# Eth_Switch_RJ45.net
KiCad netlist of a schematic drawn in Altium Designer
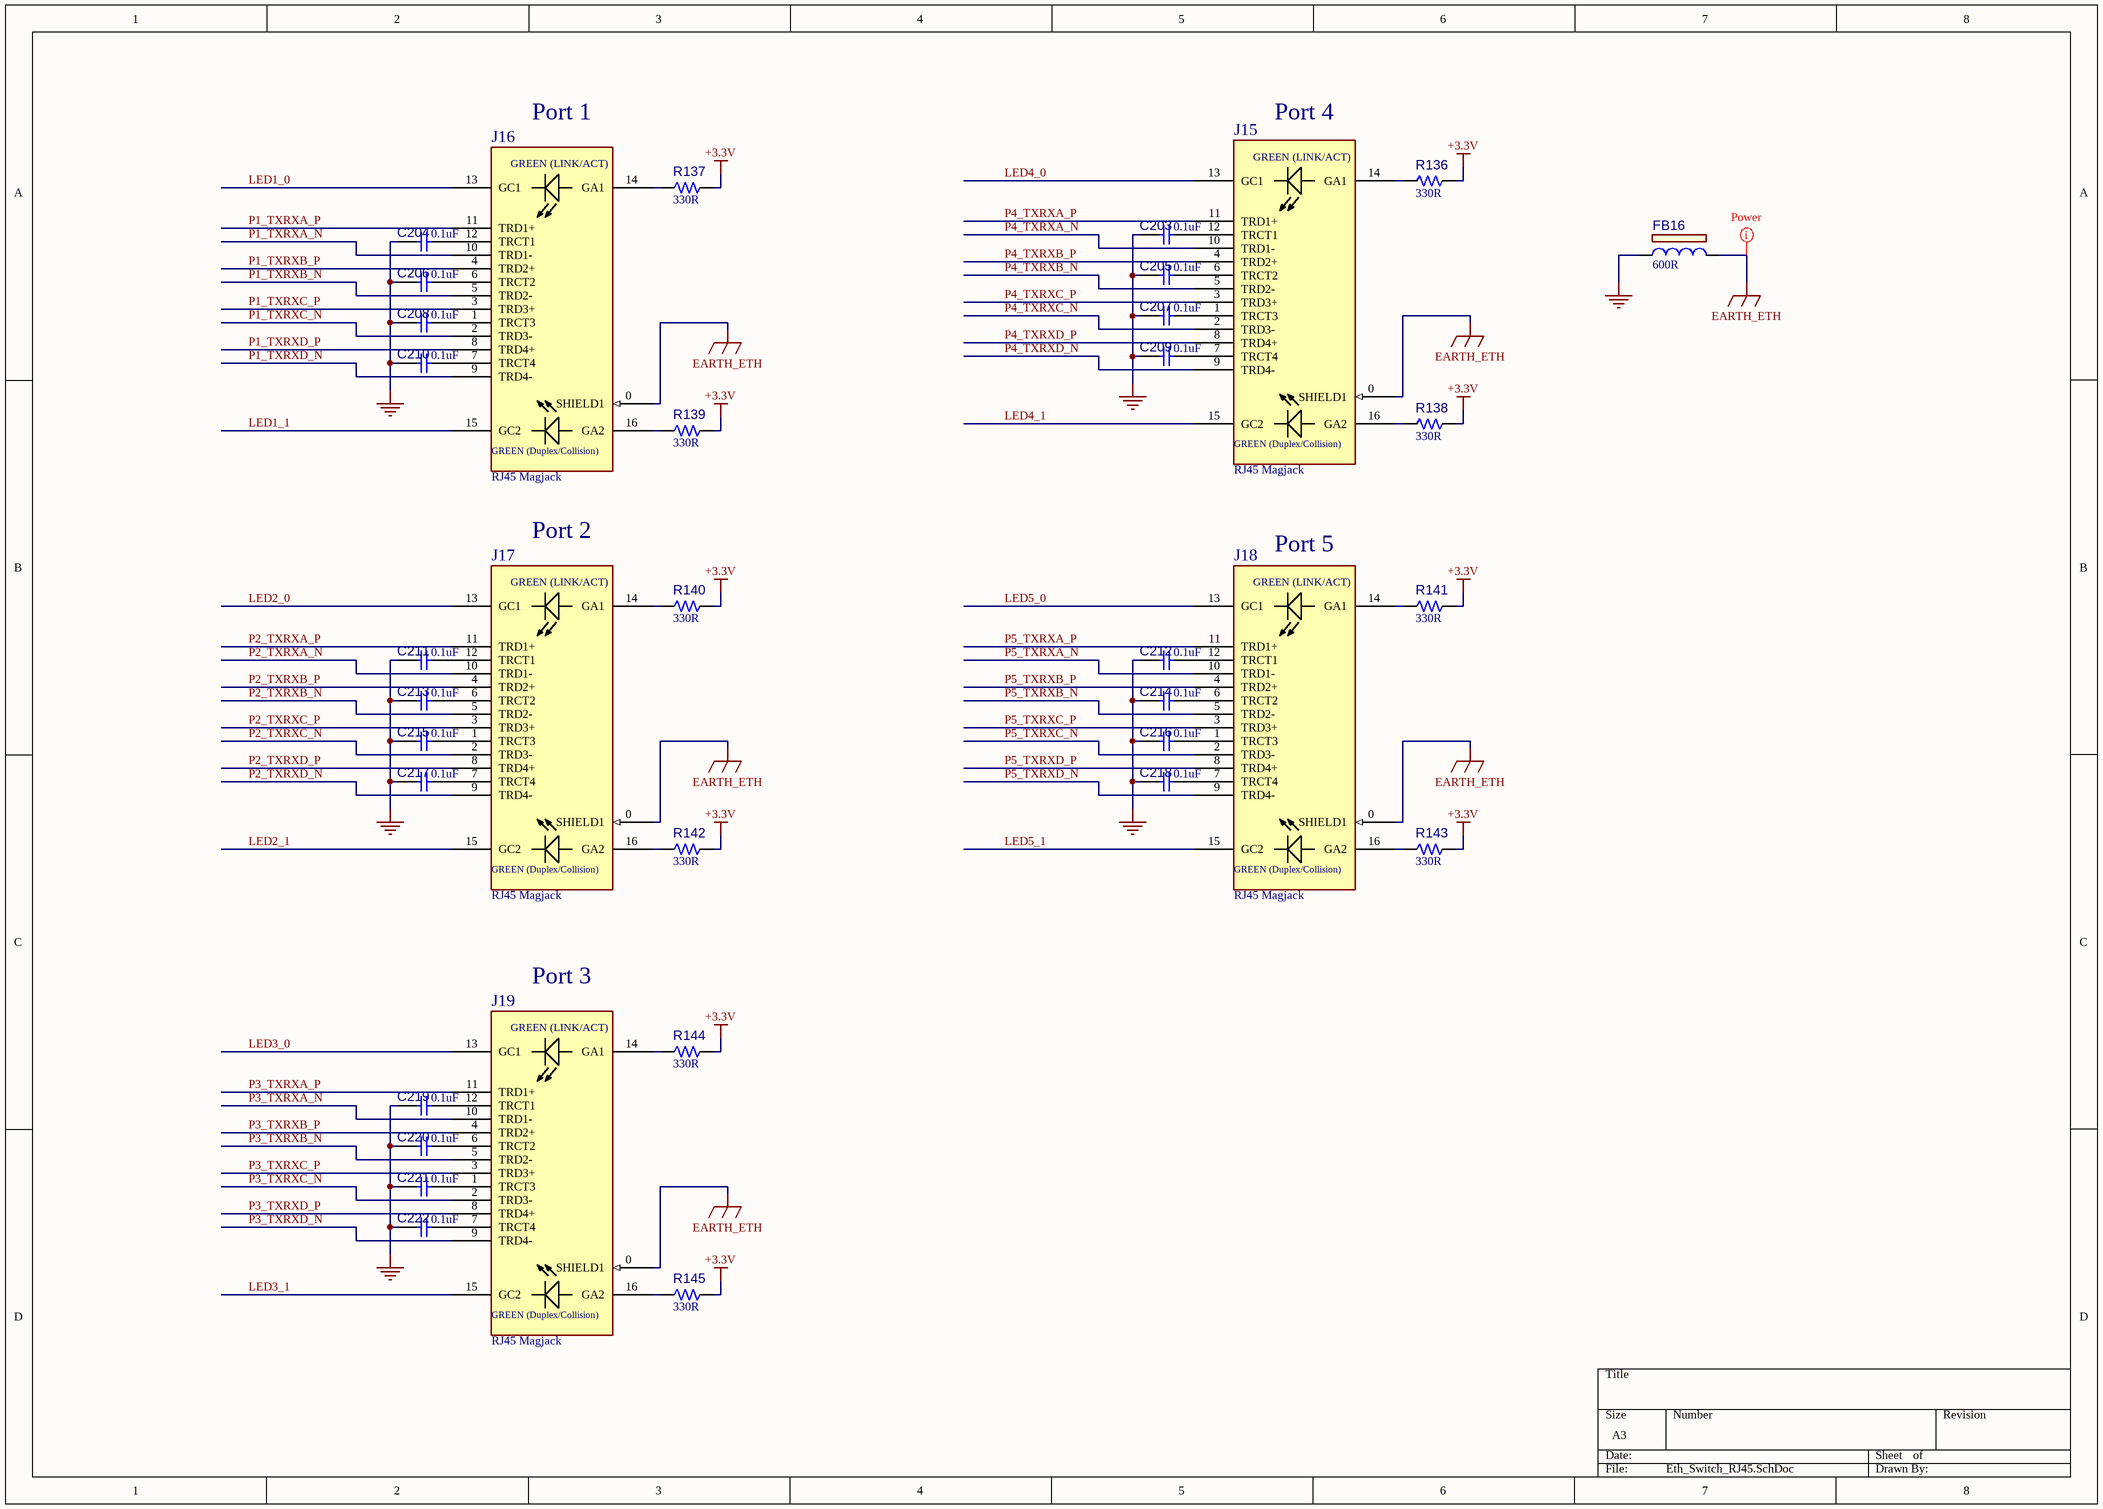
[diagram p0: Eth_Switch_RJ45.SchDoc]

(export (version "E")
  (design (tool "Eeschema 10.0.6"))
  (components
    (comp (ref "C203")
      (value "0.1uF")
      (footprint "Ultrascale_PcbLib:CAP_C_0402")
      (description "Capacitor")
      (fields
        (field (name "VOLTAGE") "50V")
        (field (name "TOLERANCE") "10%")
        (field (name "OWNER") "Jamus Griego")
      )
      (libsource (lib "Ultrascale_SchLib") (part "Capacitor NP"))
    )
    (comp (ref "C204")
      (value "0.1uF")
      (footprint "Ultrascale_PcbLib:CAP_C_0402")
      (description "Capacitor")
      (fields
        (field (name "VOLTAGE") "50V")
        (field (name "TOLERANCE") "10%")
        (field (name "OWNER") "Jamus Griego")
      )
      (libsource (lib "Ultrascale_SchLib") (part "Capacitor NP"))
    )
    (comp (ref "C205")
      (value "0.1uF")
      (footprint "Ultrascale_PcbLib:CAP_C_0402")
      (description "Capacitor")
      (fields
        (field (name "VOLTAGE") "50V")
        (field (name "TOLERANCE") "10%")
        (field (name "OWNER") "Jamus Griego")
      )
      (libsource (lib "Ultrascale_SchLib") (part "Capacitor NP"))
    )
    (comp (ref "C206")
      (value "0.1uF")
      (footprint "Ultrascale_PcbLib:CAP_C_0402")
      (description "Capacitor")
      (fields
        (field (name "VOLTAGE") "50V")
        (field (name "TOLERANCE") "10%")
        (field (name "OWNER") "Jamus Griego")
      )
      (libsource (lib "Ultrascale_SchLib") (part "Capacitor NP"))
    )
    (comp (ref "C207")
      (value "0.1uF")
      (footprint "Ultrascale_PcbLib:CAP_C_0402")
      (description "Capacitor")
      (fields
        (field (name "VOLTAGE") "50V")
        (field (name "TOLERANCE") "10%")
        (field (name "OWNER") "Jamus Griego")
      )
      (libsource (lib "Ultrascale_SchLib") (part "Capacitor NP"))
    )
    (comp (ref "C208")
      (value "0.1uF")
      (footprint "Ultrascale_PcbLib:CAP_C_0402")
      (description "Capacitor")
      (fields
        (field (name "VOLTAGE") "50V")
        (field (name "TOLERANCE") "10%")
        (field (name "OWNER") "Jamus Griego")
      )
      (libsource (lib "Ultrascale_SchLib") (part "Capacitor NP"))
    )
    (comp (ref "C209")
      (value "0.1uF")
      (footprint "Ultrascale_PcbLib:CAP_C_0402")
      (description "Capacitor")
      (fields
        (field (name "VOLTAGE") "50V")
        (field (name "TOLERANCE") "10%")
        (field (name "OWNER") "Jamus Griego")
      )
      (libsource (lib "Ultrascale_SchLib") (part "Capacitor NP"))
    )
    (comp (ref "C210")
      (value "0.1uF")
      (footprint "Ultrascale_PcbLib:CAP_C_0402")
      (description "Capacitor")
      (fields
        (field (name "VOLTAGE") "50V")
        (field (name "TOLERANCE") "10%")
        (field (name "OWNER") "Jamus Griego")
      )
      (libsource (lib "Ultrascale_SchLib") (part "Capacitor NP"))
    )
    (comp (ref "C211")
      (value "0.1uF")
      (footprint "Ultrascale_PcbLib:CAP_C_0402")
      (description "Capacitor")
      (fields
        (field (name "VOLTAGE") "50V")
        (field (name "TOLERANCE") "10%")
        (field (name "OWNER") "Jamus Griego")
      )
      (libsource (lib "Ultrascale_SchLib") (part "Capacitor NP"))
    )
    (comp (ref "C212")
      (value "0.1uF")
      (footprint "Ultrascale_PcbLib:CAP_C_0402")
      (description "Capacitor")
      (fields
        (field (name "VOLTAGE") "50V")
        (field (name "TOLERANCE") "10%")
        (field (name "OWNER") "Jamus Griego")
      )
      (libsource (lib "Ultrascale_SchLib") (part "Capacitor NP"))
    )
    (comp (ref "C213")
      (value "0.1uF")
      (footprint "Ultrascale_PcbLib:CAP_C_0402")
      (description "Capacitor")
      (fields
        (field (name "VOLTAGE") "50V")
        (field (name "TOLERANCE") "10%")
        (field (name "OWNER") "Jamus Griego")
      )
      (libsource (lib "Ultrascale_SchLib") (part "Capacitor NP"))
    )
    (comp (ref "C214")
      (value "0.1uF")
      (footprint "Ultrascale_PcbLib:CAP_C_0402")
      (description "Capacitor")
      (fields
        (field (name "VOLTAGE") "50V")
        (field (name "TOLERANCE") "10%")
        (field (name "OWNER") "Jamus Griego")
      )
      (libsource (lib "Ultrascale_SchLib") (part "Capacitor NP"))
    )
    (comp (ref "C215")
      (value "0.1uF")
      (footprint "Ultrascale_PcbLib:CAP_C_0402")
      (description "Capacitor")
      (fields
        (field (name "VOLTAGE") "50V")
        (field (name "TOLERANCE") "10%")
        (field (name "OWNER") "Jamus Griego")
      )
      (libsource (lib "Ultrascale_SchLib") (part "Capacitor NP"))
    )
    (comp (ref "C216")
      (value "0.1uF")
      (footprint "Ultrascale_PcbLib:CAP_C_0402")
      (description "Capacitor")
      (fields
        (field (name "VOLTAGE") "50V")
        (field (name "TOLERANCE") "10%")
        (field (name "OWNER") "Jamus Griego")
      )
      (libsource (lib "Ultrascale_SchLib") (part "Capacitor NP"))
    )
    (comp (ref "C217")
      (value "0.1uF")
      (footprint "Ultrascale_PcbLib:CAP_C_0402")
      (description "Capacitor")
      (fields
        (field (name "VOLTAGE") "50V")
        (field (name "TOLERANCE") "10%")
        (field (name "OWNER") "Jamus Griego")
      )
      (libsource (lib "Ultrascale_SchLib") (part "Capacitor NP"))
    )
    (comp (ref "C218")
      (value "0.1uF")
      (footprint "Ultrascale_PcbLib:CAP_C_0402")
      (description "Capacitor")
      (fields
        (field (name "VOLTAGE") "50V")
        (field (name "TOLERANCE") "10%")
        (field (name "OWNER") "Jamus Griego")
      )
      (libsource (lib "Ultrascale_SchLib") (part "Capacitor NP"))
    )
    (comp (ref "C219")
      (value "0.1uF")
      (footprint "Ultrascale_PcbLib:CAP_C_0402")
      (description "Capacitor")
      (fields
        (field (name "VOLTAGE") "50V")
        (field (name "TOLERANCE") "10%")
        (field (name "OWNER") "Jamus Griego")
      )
      (libsource (lib "Ultrascale_SchLib") (part "Capacitor NP"))
    )
    (comp (ref "C220")
      (value "0.1uF")
      (footprint "Ultrascale_PcbLib:CAP_C_0402")
      (description "Capacitor")
      (fields
        (field (name "VOLTAGE") "50V")
        (field (name "TOLERANCE") "10%")
        (field (name "OWNER") "Jamus Griego")
      )
      (libsource (lib "Ultrascale_SchLib") (part "Capacitor NP"))
    )
    (comp (ref "C221")
      (value "0.1uF")
      (footprint "Ultrascale_PcbLib:CAP_C_0402")
      (description "Capacitor")
      (fields
        (field (name "VOLTAGE") "50V")
        (field (name "TOLERANCE") "10%")
        (field (name "OWNER") "Jamus Griego")
      )
      (libsource (lib "Ultrascale_SchLib") (part "Capacitor NP"))
    )
    (comp (ref "C222")
      (value "0.1uF")
      (footprint "Ultrascale_PcbLib:CAP_C_0402")
      (description "Capacitor")
      (fields
        (field (name "VOLTAGE") "50V")
        (field (name "TOLERANCE") "10%")
        (field (name "OWNER") "Jamus Griego")
      )
      (libsource (lib "Ultrascale_SchLib") (part "Capacitor NP"))
    )
    (comp (ref "FB16")
      (value "600R")
      (footprint "Ultrascale_PcbLib:IND_C_0805")
      (fields (field (name "Comment") "Ferrite Bead") (field (name "OWNER") "Randolph Sobrepena"))
      (libsource (lib "Ultrascale_SchLib") (part "Ferrite Bead"))
    )
    (comp (ref "J15")
      (value "RJ45 Magjack")
      (footprint "Ultrascale_PcbLib:CON_MODULAR_RJ45_TH_RA_RJMG2012211A0FR")
      (description "CON RJ-45 RJMG2012211A0FR")
      (libsource (lib "Ultrascale_SchLib") (part "CON RJ-45 RJMG2012211A0FR"))
    )
    (comp (ref "J16")
      (value "RJ45 Magjack")
      (footprint "Ultrascale_PcbLib:CON_MODULAR_RJ45_TH_RA_RJMG2012211A0FR")
      (description "CON RJ-45 RJMG2012211A0FR")
      (libsource (lib "Ultrascale_SchLib") (part "CON RJ-45 RJMG2012211A0FR"))
    )
    (comp (ref "J17")
      (value "RJ45 Magjack")
      (footprint "Ultrascale_PcbLib:CON_MODULAR_RJ45_TH_RA_RJMG2012211A0FR")
      (description "CON RJ-45 RJMG2012211A0FR")
      (libsource (lib "Ultrascale_SchLib") (part "CON RJ-45 RJMG2012211A0FR"))
    )
    (comp (ref "J18")
      (value "RJ45 Magjack")
      (footprint "Ultrascale_PcbLib:CON_MODULAR_RJ45_TH_RA_RJMG2012211A0FR")
      (description "CON RJ-45 RJMG2012211A0FR")
      (libsource (lib "Ultrascale_SchLib") (part "CON RJ-45 RJMG2012211A0FR"))
    )
    (comp (ref "J19")
      (value "RJ45 Magjack")
      (footprint "Ultrascale_PcbLib:CON_MODULAR_RJ45_TH_RA_RJMG2012211A0FR")
      (description "CON RJ-45 RJMG2012211A0FR")
      (libsource (lib "Ultrascale_SchLib") (part "CON RJ-45 RJMG2012211A0FR"))
    )
    (comp (ref "R136")
      (value "330R")
      (footprint "Ultrascale_PcbLib:RES_C_0603")
      (description "Resistor")
      (fields (field (name "TOLERANCE") "5%") (field (name "VOLTAGE") "75V"))
      (libsource (lib "Ultrascale_SchLib") (part "Resistor"))
    )
    (comp (ref "R137")
      (value "330R")
      (footprint "Ultrascale_PcbLib:RES_C_0603")
      (description "Resistor")
      (fields (field (name "TOLERANCE") "5%") (field (name "VOLTAGE") "75V"))
      (libsource (lib "Ultrascale_SchLib") (part "Resistor"))
    )
    (comp (ref "R138")
      (value "330R")
      (footprint "Ultrascale_PcbLib:RES_C_0603")
      (description "Resistor")
      (fields (field (name "TOLERANCE") "5%") (field (name "VOLTAGE") "75V"))
      (libsource (lib "Ultrascale_SchLib") (part "Resistor"))
    )
    (comp (ref "R139")
      (value "330R")
      (footprint "Ultrascale_PcbLib:RES_C_0603")
      (description "Resistor")
      (fields (field (name "TOLERANCE") "5%") (field (name "VOLTAGE") "75V"))
      (libsource (lib "Ultrascale_SchLib") (part "Resistor"))
    )
    (comp (ref "R140")
      (value "330R")
      (footprint "Ultrascale_PcbLib:RES_C_0603")
      (description "Resistor")
      (fields (field (name "TOLERANCE") "5%") (field (name "VOLTAGE") "75V"))
      (libsource (lib "Ultrascale_SchLib") (part "Resistor"))
    )
    (comp (ref "R141")
      (value "330R")
      (footprint "Ultrascale_PcbLib:RES_C_0603")
      (description "Resistor")
      (fields (field (name "TOLERANCE") "5%") (field (name "VOLTAGE") "75V"))
      (libsource (lib "Ultrascale_SchLib") (part "Resistor"))
    )
    (comp (ref "R142")
      (value "330R")
      (footprint "Ultrascale_PcbLib:RES_C_0603")
      (description "Resistor")
      (fields (field (name "TOLERANCE") "5%") (field (name "VOLTAGE") "75V"))
      (libsource (lib "Ultrascale_SchLib") (part "Resistor"))
    )
    (comp (ref "R143")
      (value "330R")
      (footprint "Ultrascale_PcbLib:RES_C_0603")
      (description "Resistor")
      (fields (field (name "TOLERANCE") "5%") (field (name "VOLTAGE") "75V"))
      (libsource (lib "Ultrascale_SchLib") (part "Resistor"))
    )
    (comp (ref "R144")
      (value "330R")
      (footprint "Ultrascale_PcbLib:RES_C_0603")
      (description "Resistor")
      (fields (field (name "TOLERANCE") "5%") (field (name "VOLTAGE") "75V"))
      (libsource (lib "Ultrascale_SchLib") (part "Resistor"))
    )
    (comp (ref "R145")
      (value "330R")
      (footprint "Ultrascale_PcbLib:RES_C_0603")
      (description "Resistor")
      (fields (field (name "TOLERANCE") "5%") (field (name "VOLTAGE") "75V"))
      (libsource (lib "Ultrascale_SchLib") (part "Resistor"))
    )
  )
  (nets
    (net (code "1") (name "+3.3V") (class "Default")
      (node (ref "R136") (pin "2") (pinfunction "2_2") (pintype "passive"))
      (node (ref "R137") (pin "2") (pinfunction "2_2") (pintype "passive"))
      (node (ref "R138") (pin "2") (pinfunction "2_2") (pintype "passive"))
      (node (ref "R139") (pin "2") (pinfunction "2_2") (pintype "passive"))
      (node (ref "R140") (pin "2") (pinfunction "2_2") (pintype "passive"))
      (node (ref "R141") (pin "2") (pinfunction "2_2") (pintype "passive"))
      (node (ref "R142") (pin "2") (pinfunction "2_2") (pintype "passive"))
      (node (ref "R143") (pin "2") (pinfunction "2_2") (pintype "passive"))
      (node (ref "R144") (pin "2") (pinfunction "2_2") (pintype "passive"))
      (node (ref "R145") (pin "2") (pinfunction "2_2") (pintype "passive"))
    )
    (net (code "2") (name "/LED1_0") (class "Default")
      (node (ref "J16") (pin "13") (pinfunction "GC1_13") (pintype "passive"))
    )
    (net (code "3") (name "/LED1_1") (class "Default")
      (node (ref "J16") (pin "15") (pinfunction "GC2_15") (pintype "passive"))
    )
    (net (code "4") (name "/LED2_0") (class "Default")
      (node (ref "J17") (pin "13") (pinfunction "GC1_13") (pintype "passive"))
    )
    (net (code "5") (name "/LED2_1") (class "Default")
      (node (ref "J17") (pin "15") (pinfunction "GC2_15") (pintype "passive"))
    )
    (net (code "6") (name "/LED3_0") (class "Default")
      (node (ref "J19") (pin "13") (pinfunction "GC1_13") (pintype "passive"))
    )
    (net (code "7") (name "/LED3_1") (class "Default")
      (node (ref "J19") (pin "15") (pinfunction "GC2_15") (pintype "passive"))
    )
    (net (code "8") (name "/LED4_0") (class "Default")
      (node (ref "J15") (pin "13") (pinfunction "GC1_13") (pintype "passive"))
    )
    (net (code "9") (name "/LED4_1") (class "Default")
      (node (ref "J15") (pin "15") (pinfunction "GC2_15") (pintype "passive"))
    )
    (net (code "10") (name "/LED5_0") (class "Default")
      (node (ref "J18") (pin "13") (pinfunction "GC1_13") (pintype "passive"))
    )
    (net (code "11") (name "/LED5_1") (class "Default")
      (node (ref "J18") (pin "15") (pinfunction "GC2_15") (pintype "passive"))
    )
    (net (code "12") (name "/P1_TXRXA_N") (class "Default")
      (node (ref "J16") (pin "10") (pinfunction "TRD1-_10") (pintype "passive"))
    )
    (net (code "13") (name "/P1_TXRXA_P") (class "Default")
      (node (ref "J16") (pin "11") (pinfunction "TRD1+_11") (pintype "passive"))
    )
    (net (code "14") (name "/P1_TXRXB_N") (class "Default")
      (node (ref "J16") (pin "5") (pinfunction "TRD2-_5") (pintype "passive"))
    )
    (net (code "15") (name "/P1_TXRXB_P") (class "Default")
      (node (ref "J16") (pin "4") (pinfunction "TRD2+_4") (pintype "passive"))
    )
    (net (code "16") (name "/P1_TXRXC_N") (class "Default")
      (node (ref "J16") (pin "2") (pinfunction "TRD3-_2") (pintype "passive"))
    )
    (net (code "17") (name "/P1_TXRXC_P") (class "Default")
      (node (ref "J16") (pin "3") (pinfunction "TRD3+_3") (pintype "passive"))
    )
    (net (code "18") (name "/P1_TXRXD_N") (class "Default")
      (node (ref "J16") (pin "9") (pinfunction "TRD4-_9") (pintype "passive"))
    )
    (net (code "19") (name "/P1_TXRXD_P") (class "Default")
      (node (ref "J16") (pin "8") (pinfunction "TRD4+_8") (pintype "passive"))
    )
    (net (code "20") (name "/P2_TXRXA_N") (class "Default")
      (node (ref "J17") (pin "10") (pinfunction "TRD1-_10") (pintype "passive"))
    )
    (net (code "21") (name "/P2_TXRXA_P") (class "Default")
      (node (ref "J17") (pin "11") (pinfunction "TRD1+_11") (pintype "passive"))
    )
    (net (code "22") (name "/P2_TXRXB_N") (class "Default")
      (node (ref "J17") (pin "5") (pinfunction "TRD2-_5") (pintype "passive"))
    )
    (net (code "23") (name "/P2_TXRXB_P") (class "Default")
      (node (ref "J17") (pin "4") (pinfunction "TRD2+_4") (pintype "passive"))
    )
    (net (code "24") (name "/P2_TXRXC_N") (class "Default")
      (node (ref "J17") (pin "2") (pinfunction "TRD3-_2") (pintype "passive"))
    )
    (net (code "25") (name "/P2_TXRXC_P") (class "Default")
      (node (ref "J17") (pin "3") (pinfunction "TRD3+_3") (pintype "passive"))
    )
    (net (code "26") (name "/P2_TXRXD_N") (class "Default")
      (node (ref "J17") (pin "9") (pinfunction "TRD4-_9") (pintype "passive"))
    )
    (net (code "27") (name "/P2_TXRXD_P") (class "Default")
      (node (ref "J17") (pin "8") (pinfunction "TRD4+_8") (pintype "passive"))
    )
    (net (code "28") (name "/P3_TXRXA_N") (class "Default")
      (node (ref "J19") (pin "10") (pinfunction "TRD1-_10") (pintype "passive"))
    )
    (net (code "29") (name "/P3_TXRXA_P") (class "Default")
      (node (ref "J19") (pin "11") (pinfunction "TRD1+_11") (pintype "passive"))
    )
    (net (code "30") (name "/P3_TXRXB_N") (class "Default")
      (node (ref "J19") (pin "5") (pinfunction "TRD2-_5") (pintype "passive"))
    )
    (net (code "31") (name "/P3_TXRXB_P") (class "Default")
      (node (ref "J19") (pin "4") (pinfunction "TRD2+_4") (pintype "passive"))
    )
    (net (code "32") (name "/P3_TXRXC_N") (class "Default")
      (node (ref "J19") (pin "2") (pinfunction "TRD3-_2") (pintype "passive"))
    )
    (net (code "33") (name "/P3_TXRXC_P") (class "Default")
      (node (ref "J19") (pin "3") (pinfunction "TRD3+_3") (pintype "passive"))
    )
    (net (code "34") (name "/P3_TXRXD_N") (class "Default")
      (node (ref "J19") (pin "9") (pinfunction "TRD4-_9") (pintype "passive"))
    )
    (net (code "35") (name "/P3_TXRXD_P") (class "Default")
      (node (ref "J19") (pin "8") (pinfunction "TRD4+_8") (pintype "passive"))
    )
    (net (code "36") (name "/P4_TXRXA_N") (class "Default")
      (node (ref "J15") (pin "10") (pinfunction "TRD1-_10") (pintype "passive"))
    )
    (net (code "37") (name "/P4_TXRXA_P") (class "Default")
      (node (ref "J15") (pin "11") (pinfunction "TRD1+_11") (pintype "passive"))
    )
    (net (code "38") (name "/P4_TXRXB_N") (class "Default")
      (node (ref "J15") (pin "5") (pinfunction "TRD2-_5") (pintype "passive"))
    )
    (net (code "39") (name "/P4_TXRXB_P") (class "Default")
      (node (ref "J15") (pin "4") (pinfunction "TRD2+_4") (pintype "passive"))
    )
    (net (code "40") (name "/P4_TXRXC_N") (class "Default")
      (node (ref "J15") (pin "2") (pinfunction "TRD3-_2") (pintype "passive"))
    )
    (net (code "41") (name "/P4_TXRXC_P") (class "Default")
      (node (ref "J15") (pin "3") (pinfunction "TRD3+_3") (pintype "passive"))
    )
    (net (code "42") (name "/P4_TXRXD_N") (class "Default")
      (node (ref "J15") (pin "9") (pinfunction "TRD4-_9") (pintype "passive"))
    )
    (net (code "43") (name "/P4_TXRXD_P") (class "Default")
      (node (ref "J15") (pin "8") (pinfunction "TRD4+_8") (pintype "passive"))
    )
    (net (code "44") (name "/P5_TXRXA_N") (class "Default")
      (node (ref "J18") (pin "10") (pinfunction "TRD1-_10") (pintype "passive"))
    )
    (net (code "45") (name "/P5_TXRXA_P") (class "Default")
      (node (ref "J18") (pin "11") (pinfunction "TRD1+_11") (pintype "passive"))
    )
    (net (code "46") (name "/P5_TXRXB_N") (class "Default")
      (node (ref "J18") (pin "5") (pinfunction "TRD2-_5") (pintype "passive"))
    )
    (net (code "47") (name "/P5_TXRXB_P") (class "Default")
      (node (ref "J18") (pin "4") (pinfunction "TRD2+_4") (pintype "passive"))
    )
    (net (code "48") (name "/P5_TXRXC_N") (class "Default")
      (node (ref "J18") (pin "2") (pinfunction "TRD3-_2") (pintype "passive"))
    )
    (net (code "49") (name "/P5_TXRXC_P") (class "Default")
      (node (ref "J18") (pin "3") (pinfunction "TRD3+_3") (pintype "passive"))
    )
    (net (code "50") (name "/P5_TXRXD_N") (class "Default")
      (node (ref "J18") (pin "9") (pinfunction "TRD4-_9") (pintype "passive"))
    )
    (net (code "51") (name "/P5_TXRXD_P") (class "Default")
      (node (ref "J18") (pin "8") (pinfunction "TRD4+_8") (pintype "passive"))
    )
    (net (code "52") (name "EARTH_ETH") (class "Default")
      (node (ref "FB16") (pin "2") (pinfunction "2_2") (pintype "passive"))
      (node (ref "J15") (pin "0") (pinfunction "SHIELD1_0") (pintype "input"))
      (node (ref "J16") (pin "0") (pinfunction "SHIELD1_0") (pintype "input"))
      (node (ref "J17") (pin "0") (pinfunction "SHIELD1_0") (pintype "input"))
      (node (ref "J18") (pin "0") (pinfunction "SHIELD1_0") (pintype "input"))
      (node (ref "J19") (pin "0") (pinfunction "SHIELD1_0") (pintype "input"))
    )
    (net (code "53") (name "GND") (class "Default")
      (node (ref "C203") (pin "2") (pinfunction "2_2") (pintype "passive"))
      (node (ref "C204") (pin "2") (pinfunction "2_2") (pintype "passive"))
      (node (ref "C205") (pin "2") (pinfunction "2_2") (pintype "passive"))
      (node (ref "C206") (pin "2") (pinfunction "2_2") (pintype "passive"))
      (node (ref "C207") (pin "2") (pinfunction "2_2") (pintype "passive"))
      (node (ref "C208") (pin "2") (pinfunction "2_2") (pintype "passive"))
      (node (ref "C209") (pin "2") (pinfunction "2_2") (pintype "passive"))
      (node (ref "C210") (pin "2") (pinfunction "2_2") (pintype "passive"))
      (node (ref "C211") (pin "2") (pinfunction "2_2") (pintype "passive"))
      (node (ref "C212") (pin "2") (pinfunction "2_2") (pintype "passive"))
      (node (ref "C213") (pin "2") (pinfunction "2_2") (pintype "passive"))
      (node (ref "C214") (pin "2") (pinfunction "2_2") (pintype "passive"))
      (node (ref "C215") (pin "2") (pinfunction "2_2") (pintype "passive"))
      (node (ref "C216") (pin "2") (pinfunction "2_2") (pintype "passive"))
      (node (ref "C217") (pin "2") (pinfunction "2_2") (pintype "passive"))
      (node (ref "C218") (pin "2") (pinfunction "2_2") (pintype "passive"))
      (node (ref "C219") (pin "2") (pinfunction "2_2") (pintype "passive"))
      (node (ref "C220") (pin "2") (pinfunction "2_2") (pintype "passive"))
      (node (ref "C221") (pin "2") (pinfunction "2_2") (pintype "passive"))
      (node (ref "C222") (pin "2") (pinfunction "2_2") (pintype "passive"))
      (node (ref "FB16") (pin "1") (pinfunction "1_1") (pintype "passive"))
    )
    (net (code "54") (name "Net-(J15-GA1)") (class "Default")
      (node (ref "J15") (pin "14") (pinfunction "GA1_14") (pintype "passive"))
      (node (ref "R136") (pin "1") (pinfunction "1_1") (pintype "passive"))
    )
    (net (code "55") (name "Net-(J15-GA2)") (class "Default")
      (node (ref "J15") (pin "16") (pinfunction "GA2_16") (pintype "passive"))
      (node (ref "R138") (pin "1") (pinfunction "1_1") (pintype "passive"))
    )
    (net (code "56") (name "Net-(J15-TRCT1)") (class "Default")
      (node (ref "C203") (pin "1") (pinfunction "1_1") (pintype "passive"))
      (node (ref "J15") (pin "12") (pinfunction "TRCT1_12") (pintype "passive"))
    )
    (net (code "57") (name "Net-(J15-TRCT2)") (class "Default")
      (node (ref "C205") (pin "1") (pinfunction "1_1") (pintype "passive"))
      (node (ref "J15") (pin "6") (pinfunction "TRCT2_6") (pintype "passive"))
    )
    (net (code "58") (name "Net-(J15-TRCT3)") (class "Default")
      (node (ref "C207") (pin "1") (pinfunction "1_1") (pintype "passive"))
      (node (ref "J15") (pin "1") (pinfunction "TRCT3_1") (pintype "passive"))
    )
    (net (code "59") (name "Net-(J15-TRCT4)") (class "Default")
      (node (ref "C209") (pin "1") (pinfunction "1_1") (pintype "passive"))
      (node (ref "J15") (pin "7") (pinfunction "TRCT4_7") (pintype "passive"))
    )
    (net (code "60") (name "Net-(J16-GA1)") (class "Default")
      (node (ref "J16") (pin "14") (pinfunction "GA1_14") (pintype "passive"))
      (node (ref "R137") (pin "1") (pinfunction "1_1") (pintype "passive"))
    )
    (net (code "61") (name "Net-(J16-GA2)") (class "Default")
      (node (ref "J16") (pin "16") (pinfunction "GA2_16") (pintype "passive"))
      (node (ref "R139") (pin "1") (pinfunction "1_1") (pintype "passive"))
    )
    (net (code "62") (name "Net-(J16-TRCT1)") (class "Default")
      (node (ref "C204") (pin "1") (pinfunction "1_1") (pintype "passive"))
      (node (ref "J16") (pin "12") (pinfunction "TRCT1_12") (pintype "passive"))
    )
    (net (code "63") (name "Net-(J16-TRCT2)") (class "Default")
      (node (ref "C206") (pin "1") (pinfunction "1_1") (pintype "passive"))
      (node (ref "J16") (pin "6") (pinfunction "TRCT2_6") (pintype "passive"))
    )
    (net (code "64") (name "Net-(J16-TRCT3)") (class "Default")
      (node (ref "C208") (pin "1") (pinfunction "1_1") (pintype "passive"))
      (node (ref "J16") (pin "1") (pinfunction "TRCT3_1") (pintype "passive"))
    )
    (net (code "65") (name "Net-(J16-TRCT4)") (class "Default")
      (node (ref "C210") (pin "1") (pinfunction "1_1") (pintype "passive"))
      (node (ref "J16") (pin "7") (pinfunction "TRCT4_7") (pintype "passive"))
    )
    (net (code "66") (name "Net-(J17-GA1)") (class "Default")
      (node (ref "J17") (pin "14") (pinfunction "GA1_14") (pintype "passive"))
      (node (ref "R140") (pin "1") (pinfunction "1_1") (pintype "passive"))
    )
    (net (code "67") (name "Net-(J17-GA2)") (class "Default")
      (node (ref "J17") (pin "16") (pinfunction "GA2_16") (pintype "passive"))
      (node (ref "R142") (pin "1") (pinfunction "1_1") (pintype "passive"))
    )
    (net (code "68") (name "Net-(J17-TRCT1)") (class "Default")
      (node (ref "C211") (pin "1") (pinfunction "1_1") (pintype "passive"))
      (node (ref "J17") (pin "12") (pinfunction "TRCT1_12") (pintype "passive"))
    )
    (net (code "69") (name "Net-(J17-TRCT2)") (class "Default")
      (node (ref "C213") (pin "1") (pinfunction "1_1") (pintype "passive"))
      (node (ref "J17") (pin "6") (pinfunction "TRCT2_6") (pintype "passive"))
    )
    (net (code "70") (name "Net-(J17-TRCT3)") (class "Default")
      (node (ref "C215") (pin "1") (pinfunction "1_1") (pintype "passive"))
      (node (ref "J17") (pin "1") (pinfunction "TRCT3_1") (pintype "passive"))
    )
    (net (code "71") (name "Net-(J17-TRCT4)") (class "Default")
      (node (ref "C217") (pin "1") (pinfunction "1_1") (pintype "passive"))
      (node (ref "J17") (pin "7") (pinfunction "TRCT4_7") (pintype "passive"))
    )
    (net (code "72") (name "Net-(J18-GA1)") (class "Default")
      (node (ref "J18") (pin "14") (pinfunction "GA1_14") (pintype "passive"))
      (node (ref "R141") (pin "1") (pinfunction "1_1") (pintype "passive"))
    )
    (net (code "73") (name "Net-(J18-GA2)") (class "Default")
      (node (ref "J18") (pin "16") (pinfunction "GA2_16") (pintype "passive"))
      (node (ref "R143") (pin "1") (pinfunction "1_1") (pintype "passive"))
    )
    (net (code "74") (name "Net-(J18-TRCT1)") (class "Default")
      (node (ref "C212") (pin "1") (pinfunction "1_1") (pintype "passive"))
      (node (ref "J18") (pin "12") (pinfunction "TRCT1_12") (pintype "passive"))
    )
    (net (code "75") (name "Net-(J18-TRCT2)") (class "Default")
      (node (ref "C214") (pin "1") (pinfunction "1_1") (pintype "passive"))
      (node (ref "J18") (pin "6") (pinfunction "TRCT2_6") (pintype "passive"))
    )
    (net (code "76") (name "Net-(J18-TRCT3)") (class "Default")
      (node (ref "C216") (pin "1") (pinfunction "1_1") (pintype "passive"))
      (node (ref "J18") (pin "1") (pinfunction "TRCT3_1") (pintype "passive"))
    )
    (net (code "77") (name "Net-(J18-TRCT4)") (class "Default")
      (node (ref "C218") (pin "1") (pinfunction "1_1") (pintype "passive"))
      (node (ref "J18") (pin "7") (pinfunction "TRCT4_7") (pintype "passive"))
    )
    (net (code "78") (name "Net-(J19-GA1)") (class "Default")
      (node (ref "J19") (pin "14") (pinfunction "GA1_14") (pintype "passive"))
      (node (ref "R144") (pin "1") (pinfunction "1_1") (pintype "passive"))
    )
    (net (code "79") (name "Net-(J19-GA2)") (class "Default")
      (node (ref "J19") (pin "16") (pinfunction "GA2_16") (pintype "passive"))
      (node (ref "R145") (pin "1") (pinfunction "1_1") (pintype "passive"))
    )
    (net (code "80") (name "Net-(J19-TRCT1)") (class "Default")
      (node (ref "C219") (pin "1") (pinfunction "1_1") (pintype "passive"))
      (node (ref "J19") (pin "12") (pinfunction "TRCT1_12") (pintype "passive"))
    )
    (net (code "81") (name "Net-(J19-TRCT2)") (class "Default")
      (node (ref "C220") (pin "1") (pinfunction "1_1") (pintype "passive"))
      (node (ref "J19") (pin "6") (pinfunction "TRCT2_6") (pintype "passive"))
    )
    (net (code "82") (name "Net-(J19-TRCT3)") (class "Default")
      (node (ref "C221") (pin "1") (pinfunction "1_1") (pintype "passive"))
      (node (ref "J19") (pin "1") (pinfunction "TRCT3_1") (pintype "passive"))
    )
    (net (code "83") (name "Net-(J19-TRCT4)") (class "Default")
      (node (ref "C222") (pin "1") (pinfunction "1_1") (pintype "passive"))
      (node (ref "J19") (pin "7") (pinfunction "TRCT4_7") (pintype "passive"))
    )
  )
)
